# AMFS_PCB4.net
KiCad netlist of a schematic drawn in EAGLE
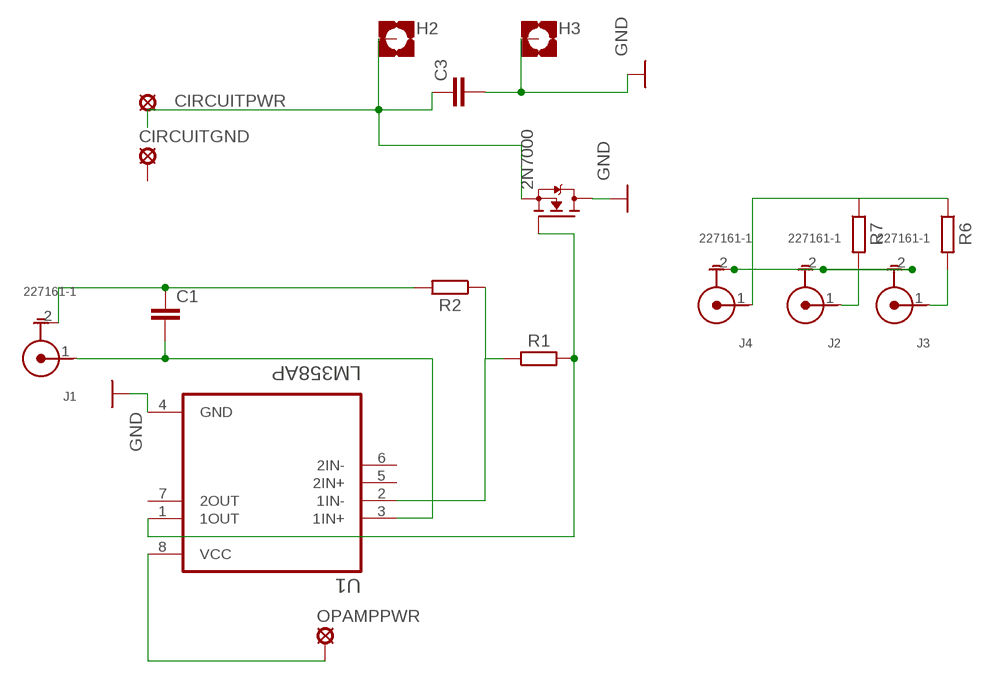
[diagram p0: schematic, sheet 1]

(export (version "E")
  (design (tool "Eeschema 10.0.6"))
  (components
    (comp (ref "C1")
      (value "C5/3.5")
      (footprint "eagle-import:C5B3.5")
      (libsource (lib "eagle-import") (part "C5/3.5"))
    )
    (comp (ref "C3")
      (value "C5/3.5")
      (footprint "eagle-import:C5B3.5")
      (libsource (lib "eagle-import") (part "C5/3.5"))
    )
    (comp (ref "CIRCUITGND")
      (value "LSP10")
      (footprint "eagle-import:LSP10")
      (libsource (lib "eagle-import") (part "LSP10"))
    )
    (comp (ref "CIRCUITPWR")
      (value "MCS10B")
      (footprint "eagle-import:MCS10B")
      (libsource (lib "eagle-import") (part "MCS10B"))
    )
    (comp (ref "H2")
      (value "MOUNT-PAD-SQUARE2.8")
      (footprint "eagle-import:2,8-PAD-SQUARE")
      (libsource (lib "eagle-import") (part "MOUNT-PAD-SQUARE2.8"))
    )
    (comp (ref "H3")
      (value "MOUNT-PAD-SQUARE2.8")
      (footprint "eagle-import:2,8-PAD-SQUARE")
      (libsource (lib "eagle-import") (part "MOUNT-PAD-SQUARE2.8"))
    )
    (comp (ref "J1")
      (value "227161-1")
      (footprint "eagle-import:TE_227161-1")
      (fields (field (name "MF") "TE Connectivity"))
      (libsource (lib "eagle-import") (part "227161-1"))
    )
    (comp (ref "J2")
      (value "227161-1")
      (footprint "eagle-import:TE_227161-1")
      (fields (field (name "MF") "TE Connectivity"))
      (libsource (lib "eagle-import") (part "227161-1"))
    )
    (comp (ref "J3")
      (value "227161-1")
      (footprint "eagle-import:TE_227161-1")
      (fields (field (name "MF") "TE Connectivity"))
      (libsource (lib "eagle-import") (part "227161-1"))
    )
    (comp (ref "J4")
      (value "227161-1")
      (footprint "eagle-import:TE_227161-1")
      (fields (field (name "MF") "TE Connectivity"))
      (libsource (lib "eagle-import") (part "227161-1"))
    )
    (comp (ref "OPAMPPWR")
      (value "LSP10")
      (footprint "eagle-import:LSP10")
      (libsource (lib "eagle-import") (part "LSP10"))
    )
    (comp (ref "R1")
      (value "R_AXIAL-7.2MM-PITCH")
      (footprint "eagle-import:RESAD724W46L381D178B")
      (libsource (lib "eagle-import") (part "RAXIAL-7.2MM-PITCH_"))
    )
    (comp (ref "R2")
      (value "R_AXIAL-7.2MM-PITCH")
      (footprint "eagle-import:RESAD724W46L381D178B")
      (libsource (lib "eagle-import") (part "RAXIAL-7.2MM-PITCH_"))
    )
    (comp (ref "R6")
      (value "R_AXIAL-7.2MM-PITCH")
      (footprint "eagle-import:RESAD724W46L381D178B")
      (libsource (lib "eagle-import") (part "RAXIAL-7.2MM-PITCH_"))
    )
    (comp (ref "R7")
      (value "R_AXIAL-7.2MM-PITCH")
      (footprint "eagle-import:RESAD724W46L381D178B")
      (libsource (lib "eagle-import") (part "RAXIAL-7.2MM-PITCH_"))
    )
    (comp (ref "SHUNT")
      (value "2N7000")
      (footprint "eagle-import:TO92-")
      (fields (field (name "MF") "STMicroelectronics"))
      (libsource (lib "eagle-import") (part "2N7000"))
    )
    (comp (ref "U1")
      (value "LM358AP")
      (footprint "eagle-import:DIP794W45P254L959H508Q8")
      (fields (field (name "MF") "Texas Instruments"))
      (libsource (lib "eagle-import") (part "LM358AP"))
    )
  )
  (nets
    (net (code "1") (name "GND") (class "Default")
      (node (ref "C3") (pin "2") (pinfunction "2_2") (pintype "passive"))
      (node (ref "H3") (pin "B2,8") (pinfunction "MOUNT_B2,8") (pintype "passive"))
      (node (ref "SHUNT") (pin "1") (pinfunction "D_1") (pintype "passive"))
      (node (ref "U1") (pin "4") (pinfunction "GND_4") (pintype "power_in"))
    )
    (net (code "2") (name "Net-(H2-MOUNT)") (class "Default")
      (node (ref "C3") (pin "1") (pinfunction "1_1") (pintype "passive"))
      (node (ref "CIRCUITPWR") (pin "MP") (pinfunction "MP_MP") (pintype "passive"))
      (node (ref "H2") (pin "B2,8") (pinfunction "MOUNT_B2,8") (pintype "passive"))
      (node (ref "SHUNT") (pin "3") (pinfunction "S_3") (pintype "passive"))
    )
    (net (code "3") (name "Net-(J1-C)") (class "Default")
      (node (ref "C1") (pin "2") (pinfunction "2_2") (pintype "passive"))
      (node (ref "J1") (pin "1") (pinfunction "C_1") (pintype "passive"))
      (node (ref "U1") (pin "3") (pinfunction "1IN+_3") (pintype "input"))
    )
    (net (code "4") (name "Net-(J1-G)") (class "Default")
      (node (ref "C1") (pin "1") (pinfunction "1_1") (pintype "passive"))
      (node (ref "J1") (pin "2") (pinfunction "G_2") (pintype "power_in"))
      (node (ref "R2") (pin "2") (pinfunction "2_2") (pintype "passive"))
    )
    (net (code "5") (name "Net-(J2-C)") (class "Default")
      (node (ref "J2") (pin "1") (pinfunction "C_1") (pintype "passive"))
      (node (ref "R7") (pin "2") (pinfunction "2_2") (pintype "passive"))
    )
    (net (code "6") (name "Net-(J2-G)") (class "Default")
      (node (ref "J2") (pin "2") (pinfunction "G_2") (pintype "power_in"))
      (node (ref "J3") (pin "2") (pinfunction "G_2") (pintype "power_in"))
      (node (ref "J4") (pin "2") (pinfunction "G_2") (pintype "power_in"))
    )
    (net (code "7") (name "Net-(J3-C)") (class "Default")
      (node (ref "J3") (pin "1") (pinfunction "C_1") (pintype "passive"))
      (node (ref "R6") (pin "2") (pinfunction "2_2") (pintype "passive"))
    )
    (net (code "8") (name "Net-(J4-C)") (class "Default")
      (node (ref "J4") (pin "1") (pinfunction "C_1") (pintype "passive"))
      (node (ref "R6") (pin "1") (pinfunction "1_1") (pintype "passive"))
      (node (ref "R7") (pin "1") (pinfunction "1_1") (pintype "passive"))
    )
    (net (code "9") (name "Net-(SHUNT-G)") (class "Default")
      (node (ref "R1") (pin "2") (pinfunction "2_2") (pintype "passive"))
      (node (ref "SHUNT") (pin "2") (pinfunction "G_2") (pintype "passive"))
      (node (ref "U1") (pin "1") (pinfunction "1OUT_1") (pintype "output"))
    )
    (net (code "10") (name "Net-(U1-1IN-)") (class "Default")
      (node (ref "R1") (pin "1") (pinfunction "1_1") (pintype "passive"))
      (node (ref "R2") (pin "1") (pinfunction "1_1") (pintype "passive"))
      (node (ref "U1") (pin "2") (pinfunction "1IN-_2") (pintype "input"))
    )
    (net (code "11") (name "Net-(U1-VCC)") (class "Default")
      (node (ref "OPAMPPWR") (pin "MP") (pinfunction "MP_MP") (pintype "passive"))
      (node (ref "U1") (pin "8") (pinfunction "VCC_8") (pintype "power_in"))
    )
    (net (code "12") (name "unconnected-(CIRCUITGND-PadMP)") (class "Default")
      (node (ref "CIRCUITGND") (pin "MP") (pinfunction "MP_MP") (pintype "passive"))
    )
    (net (code "13") (name "unconnected-(U1-2IN+-Pad5)") (class "Default")
      (node (ref "U1") (pin "5") (pinfunction "2IN+_5") (pintype "input"))
    )
    (net (code "14") (name "unconnected-(U1-2IN--Pad6)") (class "Default")
      (node (ref "U1") (pin "6") (pinfunction "2IN-_6") (pintype "input"))
    )
    (net (code "15") (name "unconnected-(U1-2OUT-Pad7)") (class "Default")
      (node (ref "U1") (pin "7") (pinfunction "2OUT_7") (pintype "output"))
    )
  )
)
